# NG2094_IR_Dot_Projector.net
KiCad netlist of a schematic drawn in Altium Designer
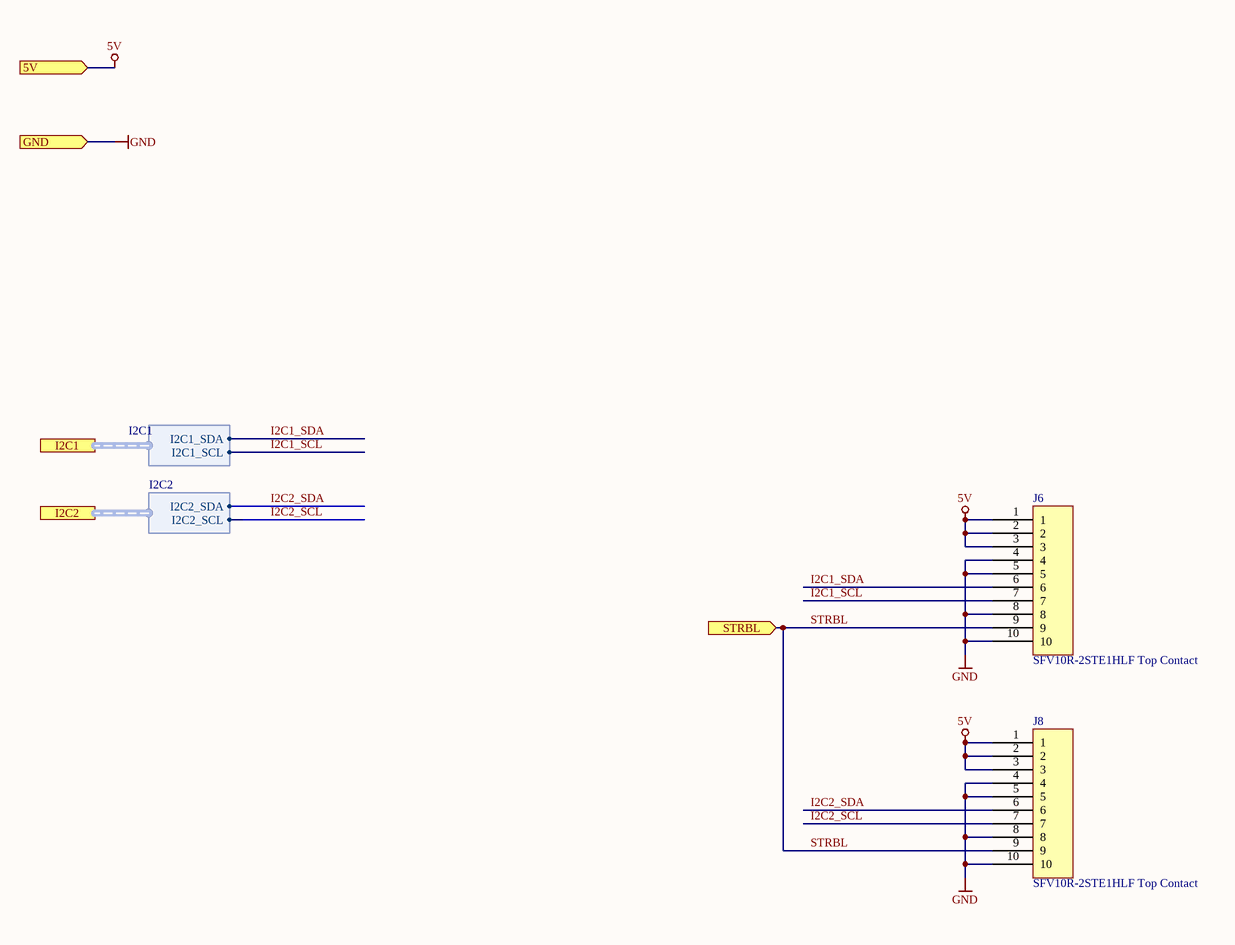
[diagram p0: NG2094_IR_Dot_Projector.SchDoc]

(export (version "E")
  (design (tool "Eeschema 10.0.6"))
  (components
    (comp (ref "J6")
      (value "SFV10R-2STE1HLF Top Contact")
      (footprint "SFV10R-2STE1HLF")
      (description "CONN FFC TOP 10POS 0.50MM R/A")
      (libsource (lib "LuxonisMaster") (part "SFV10R-2STE1HLF"))
    )
    (comp (ref "J8")
      (value "SFV10R-2STE1HLF Top Contact")
      (footprint "SFV10R-2STE1HLF")
      (description "CONN FFC TOP 10POS 0.50MM R/A")
      (libsource (lib "LuxonisMaster") (part "SFV10R-2STE1HLF"))
    )
  )
  (nets
    (net (code "3") (name "/I2C1_SCL") (class "Default")
      (node (ref "J6") (pin "7") (pinfunction "7_7") (pintype "passive"))
    )
    (net (code "4") (name "/I2C1_SDA") (class "Default")
      (node (ref "J6") (pin "6") (pinfunction "6_6") (pintype "passive"))
    )
    (net (code "5") (name "/I2C2_SCL") (class "Default")
      (node (ref "J8") (pin "7") (pinfunction "7_7") (pintype "passive"))
    )
    (net (code "6") (name "/I2C2_SDA") (class "Default")
      (node (ref "J8") (pin "6") (pinfunction "6_6") (pintype "passive"))
    )
    (net (code "7") (name "/STRBL") (class "Default")
      (node (ref "J6") (pin "9") (pinfunction "9_9") (pintype "passive"))
      (node (ref "J8") (pin "9") (pinfunction "9_9") (pintype "passive"))
    )
    (net (code "10") (name "5V") (class "Default")
      (node (ref "J6") (pin "1") (pinfunction "1_1") (pintype "passive"))
      (node (ref "J6") (pin "2") (pinfunction "2_2") (pintype "passive"))
      (node (ref "J6") (pin "3") (pinfunction "3_3") (pintype "passive"))
      (node (ref "J8") (pin "1") (pinfunction "1_1") (pintype "passive"))
      (node (ref "J8") (pin "2") (pinfunction "2_2") (pintype "passive"))
      (node (ref "J8") (pin "3") (pinfunction "3_3") (pintype "passive"))
    )
    (net (code "11") (name "GND") (class "Default")
      (node (ref "J6") (pin "10") (pinfunction "10_10") (pintype "passive"))
      (node (ref "J6") (pin "4") (pinfunction "4_4") (pintype "passive"))
      (node (ref "J6") (pin "5") (pinfunction "5_5") (pintype "passive"))
      (node (ref "J6") (pin "8") (pinfunction "8_8") (pintype "passive"))
      (node (ref "J8") (pin "10") (pinfunction "10_10") (pintype "passive"))
      (node (ref "J8") (pin "4") (pinfunction "4_4") (pintype "passive"))
      (node (ref "J8") (pin "5") (pinfunction "5_5") (pintype "passive"))
      (node (ref "J8") (pin "8") (pinfunction "8_8") (pintype "passive"))
    )
  )
)
